# pcb_telemetria_inicial.net
KiCad netlist of a schematic drawn in EAGLE
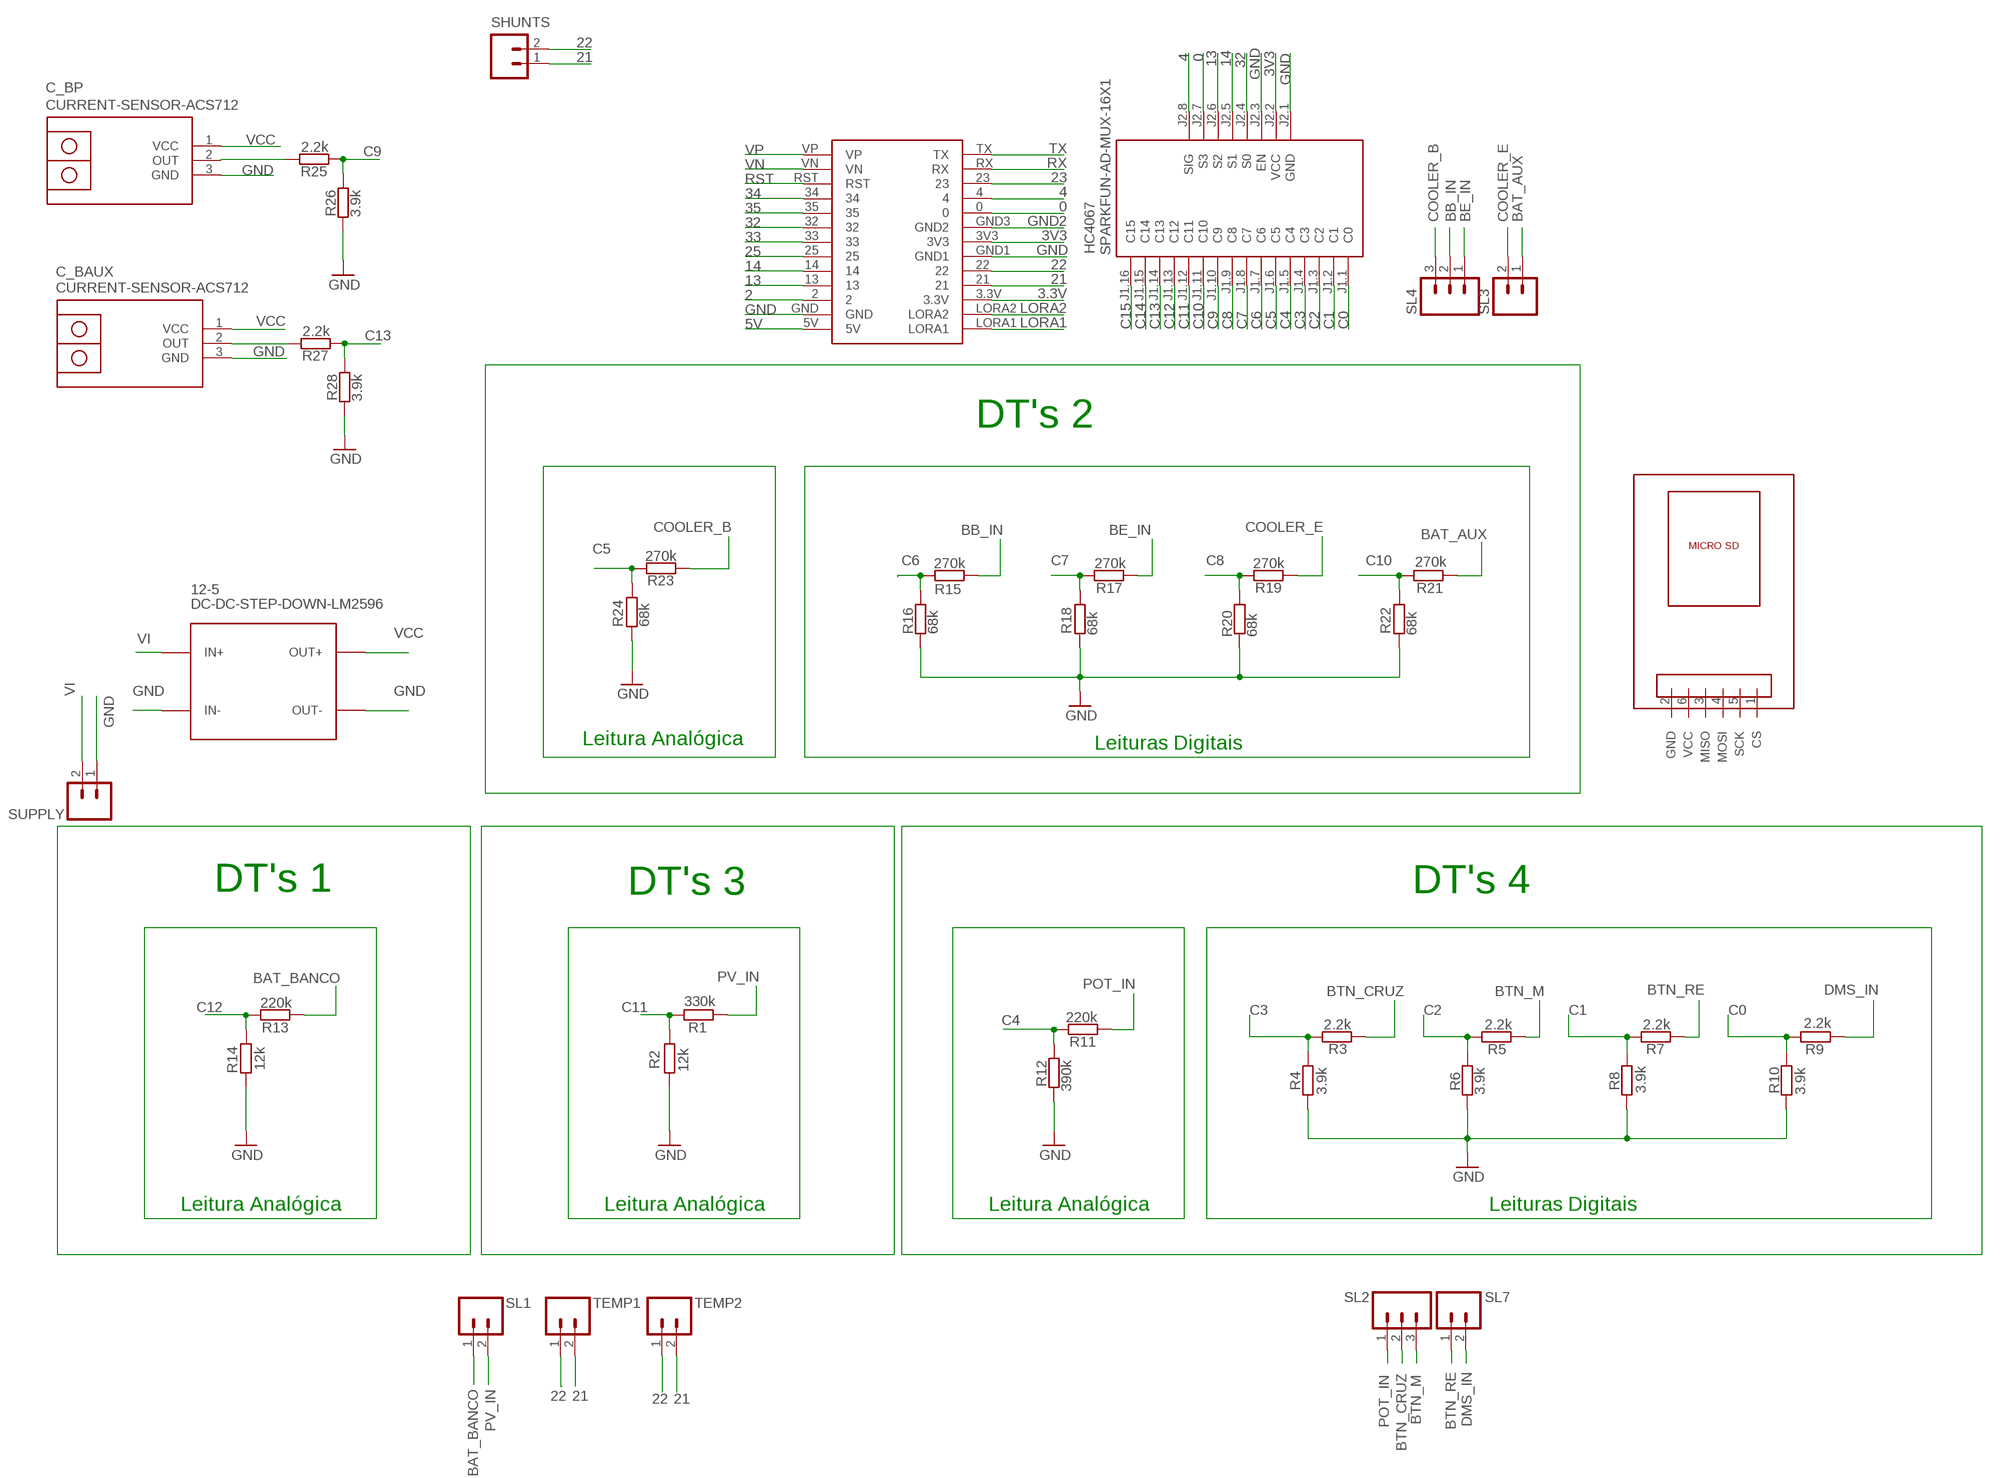
[diagram p0: schematic, sheet 1]

(export (version "E")
  (design (tool "Eeschema 10.0.6"))
  (components
    (comp (ref "12-5")
      (value "DC-DC-STEP-DOWN-LM2596")
      (footprint "eagle-import:DC-DC-STEP-DOWN-LM2596")
      (libsource (lib "eagle-import") (part "DC-DC-STEP-DOWN-LM2596"))
    )
    (comp (ref "C_BAUX")
      (value "CURRENT-SENSOR-ACS712")
      (footprint "eagle-import:CURRENT-SENSOR-ACS712")
      (libsource (lib "eagle-import") (part "CURRENT-SENSOR-ACS712"))
    )
    (comp (ref "C_BP")
      (value "CURRENT-SENSOR-ACS712")
      (footprint "eagle-import:CURRENT-SENSOR-ACS712")
      (libsource (lib "eagle-import") (part "CURRENT-SENSOR-ACS712"))
    )
    (comp (ref "HC4067")
      (value "SPARKFUN-AD-MUX-16X1")
      (footprint "eagle-import:SPARKFUN-AD-MUX-16X1")
      (libsource (lib "eagle-import") (part "SPARKFUN-AD-MUX-16X1"))
    )
    (comp (ref "R1")
      (value "330k")
      (footprint "eagle-import:0204_7")
      (libsource (lib "eagle-import") (part "R-EU_0204/7"))
    )
    (comp (ref "R2")
      (value "12k")
      (footprint "eagle-import:0204_7")
      (libsource (lib "eagle-import") (part "R-EU_0204/7"))
    )
    (comp (ref "R3")
      (value "2.2k")
      (footprint "eagle-import:0204_7")
      (libsource (lib "eagle-import") (part "R-EU_0204/7"))
    )
    (comp (ref "R4")
      (value "3.9k")
      (footprint "eagle-import:0204_7")
      (libsource (lib "eagle-import") (part "R-EU_0204/7"))
    )
    (comp (ref "R5")
      (value "2.2k")
      (footprint "eagle-import:0204_7")
      (libsource (lib "eagle-import") (part "R-EU_0204/7"))
    )
    (comp (ref "R6")
      (value "3.9k")
      (footprint "eagle-import:0204_7")
      (libsource (lib "eagle-import") (part "R-EU_0204/7"))
    )
    (comp (ref "R7")
      (value "2.2k")
      (footprint "eagle-import:0204_7")
      (libsource (lib "eagle-import") (part "R-EU_0204/7"))
    )
    (comp (ref "R8")
      (value "3.9k")
      (footprint "eagle-import:0204_7")
      (libsource (lib "eagle-import") (part "R-EU_0204/7"))
    )
    (comp (ref "R9")
      (value "2.2k")
      (footprint "eagle-import:0204_7")
      (libsource (lib "eagle-import") (part "R-EU_0204/7"))
    )
    (comp (ref "R10")
      (value "3.9k")
      (footprint "eagle-import:0204_7")
      (libsource (lib "eagle-import") (part "R-EU_0204/7"))
    )
    (comp (ref "R11")
      (value "220k")
      (footprint "eagle-import:0204_7")
      (libsource (lib "eagle-import") (part "R-EU_0204/7"))
    )
    (comp (ref "R12")
      (value "390k")
      (footprint "eagle-import:0204_7")
      (libsource (lib "eagle-import") (part "R-EU_0204/7"))
    )
    (comp (ref "R13")
      (value "220k")
      (footprint "eagle-import:0204_7")
      (libsource (lib "eagle-import") (part "R-EU_0204/7"))
    )
    (comp (ref "R14")
      (value "12k")
      (footprint "eagle-import:0204_7")
      (libsource (lib "eagle-import") (part "R-EU_0204/7"))
    )
    (comp (ref "R15")
      (value "270k")
      (footprint "eagle-import:0204_7")
      (libsource (lib "eagle-import") (part "R-EU_0204/7"))
    )
    (comp (ref "R16")
      (value "68k")
      (footprint "eagle-import:0204_7")
      (libsource (lib "eagle-import") (part "R-EU_0204/7"))
    )
    (comp (ref "R17")
      (value "270k")
      (footprint "eagle-import:0204_7")
      (libsource (lib "eagle-import") (part "R-EU_0204/7"))
    )
    (comp (ref "R18")
      (value "68k")
      (footprint "eagle-import:0204_7")
      (libsource (lib "eagle-import") (part "R-EU_0204/7"))
    )
    (comp (ref "R19")
      (value "270k")
      (footprint "eagle-import:0204_7")
      (libsource (lib "eagle-import") (part "R-EU_0204/7"))
    )
    (comp (ref "R20")
      (value "68k")
      (footprint "eagle-import:0204_7")
      (libsource (lib "eagle-import") (part "R-EU_0204/7"))
    )
    (comp (ref "R21")
      (value "270k")
      (footprint "eagle-import:0204_7")
      (libsource (lib "eagle-import") (part "R-EU_0204/7"))
    )
    (comp (ref "R22")
      (value "68k")
      (footprint "eagle-import:0204_7")
      (libsource (lib "eagle-import") (part "R-EU_0204/7"))
    )
    (comp (ref "R23")
      (value "270k")
      (footprint "eagle-import:0204_7")
      (libsource (lib "eagle-import") (part "R-EU_0204/7"))
    )
    (comp (ref "R24")
      (value "68k")
      (footprint "eagle-import:0204_7")
      (libsource (lib "eagle-import") (part "R-EU_0204/7"))
    )
    (comp (ref "R25")
      (value "2.2k")
      (footprint "eagle-import:0204_7")
      (libsource (lib "eagle-import") (part "R-EU_0204/7"))
    )
    (comp (ref "R26")
      (value "3.9k")
      (footprint "eagle-import:0204_7")
      (libsource (lib "eagle-import") (part "R-EU_0204/7"))
    )
    (comp (ref "R27")
      (value "2.2k")
      (footprint "eagle-import:0204_7")
      (libsource (lib "eagle-import") (part "R-EU_0204/7"))
    )
    (comp (ref "R28")
      (value "3.9k")
      (footprint "eagle-import:0204_7")
      (libsource (lib "eagle-import") (part "R-EU_0204/7"))
    )
    (comp (ref "SHUNTS")
      (value "M02")
      (footprint "eagle-import:02P")
      (libsource (lib "eagle-import") (part "M02"))
    )
    (comp (ref "SL1")
      (value "M02")
      (footprint "eagle-import:02P")
      (libsource (lib "eagle-import") (part "M02"))
    )
    (comp (ref "SL2")
      (value "M03")
      (footprint "eagle-import:03P")
      (libsource (lib "eagle-import") (part "M03"))
    )
    (comp (ref "SL3")
      (value "M02")
      (footprint "eagle-import:02P")
      (libsource (lib "eagle-import") (part "M02"))
    )
    (comp (ref "SL4")
      (value "M03")
      (footprint "eagle-import:03P")
      (libsource (lib "eagle-import") (part "M03"))
    )
    (comp (ref "SL7")
      (value "M02")
      (footprint "eagle-import:02P")
      (libsource (lib "eagle-import") (part "M02"))
    )
    (comp (ref "SUPPLY")
      (value "M02")
      (footprint "eagle-import:02P")
      (libsource (lib "eagle-import") (part "M02"))
    )
    (comp (ref "TEMP1")
      (value "M02")
      (footprint "eagle-import:02P")
      (libsource (lib "eagle-import") (part "M02"))
    )
    (comp (ref "TEMP2")
      (value "M02")
      (footprint "eagle-import:02P")
      (libsource (lib "eagle-import") (part "M02"))
    )
    (comp (ref "U$1")
      (value "TTGOBEAM")
      (footprint "eagle-import:TTGOBEAM")
      (libsource (lib "eagle-import") (part "TTGOBEAM"))
    )
    (comp (ref "U$2")
      (value "MICRO_SD_MODULE")
      (footprint "eagle-import:MICRO_SD")
      (libsource (lib "eagle-import") (part "MICRO_SD_MODULE"))
    )
  )
  (nets
    (net (code "1") (name "/0") (class "Default")
      (node (ref "HC4067") (pin "J2.7") (pinfunction "S3_J2.7") (pintype "bidirectional"))
      (node (ref "U$1") (pin "0") (pinfunction "0_0") (pintype "bidirectional"))
    )
    (net (code "2") (name "/2") (class "Default")
      (node (ref "U$1") (pin "2") (pinfunction "2_2") (pintype "bidirectional"))
    )
    (net (code "3") (name "/3.3V") (class "Default")
      (node (ref "U$1") (pin "3.3V") (pinfunction "3.3V_3.3V") (pintype "bidirectional"))
    )
    (net (code "4") (name "/3V3") (class "Default")
      (node (ref "HC4067") (pin "J2.2") (pinfunction "VCC_J2.2") (pintype "power_in"))
      (node (ref "U$1") (pin "3V3") (pinfunction "3V3_3V3") (pintype "bidirectional"))
    )
    (net (code "5") (name "/4") (class "Default")
      (node (ref "HC4067") (pin "J2.8") (pinfunction "SIG_J2.8") (pintype "bidirectional"))
      (node (ref "U$1") (pin "4") (pinfunction "4_4") (pintype "bidirectional"))
    )
    (net (code "6") (name "/5V") (class "Default")
      (node (ref "U$1") (pin "5V") (pinfunction "5V_5V") (pintype "bidirectional"))
    )
    (net (code "7") (name "/13") (class "Default")
      (node (ref "HC4067") (pin "J2.6") (pinfunction "S2_J2.6") (pintype "bidirectional"))
      (node (ref "U$1") (pin "13") (pinfunction "13_13") (pintype "bidirectional"))
    )
    (net (code "8") (name "/14") (class "Default")
      (node (ref "HC4067") (pin "J2.5") (pinfunction "S1_J2.5") (pintype "bidirectional"))
      (node (ref "U$1") (pin "14") (pinfunction "14_14") (pintype "bidirectional"))
    )
    (net (code "9") (name "/21") (class "Default")
      (node (ref "SHUNTS") (pin "1") (pinfunction "1_1") (pintype "passive"))
      (node (ref "TEMP1") (pin "2") (pinfunction "2_2") (pintype "passive"))
      (node (ref "TEMP2") (pin "2") (pinfunction "2_2") (pintype "passive"))
      (node (ref "U$1") (pin "21") (pinfunction "21_21") (pintype "bidirectional"))
    )
    (net (code "10") (name "/22") (class "Default")
      (node (ref "SHUNTS") (pin "2") (pinfunction "2_2") (pintype "passive"))
      (node (ref "TEMP1") (pin "1") (pinfunction "1_1") (pintype "passive"))
      (node (ref "TEMP2") (pin "1") (pinfunction "1_1") (pintype "passive"))
      (node (ref "U$1") (pin "22") (pinfunction "22_22") (pintype "bidirectional"))
    )
    (net (code "11") (name "/23") (class "Default")
      (node (ref "U$1") (pin "23") (pinfunction "23_23") (pintype "bidirectional"))
    )
    (net (code "12") (name "/25") (class "Default")
      (node (ref "U$1") (pin "25") (pinfunction "25_25") (pintype "bidirectional"))
    )
    (net (code "13") (name "/32") (class "Default")
      (node (ref "HC4067") (pin "J2.4") (pinfunction "S0_J2.4") (pintype "bidirectional"))
      (node (ref "U$1") (pin "32") (pinfunction "32_32") (pintype "bidirectional"))
    )
    (net (code "14") (name "/33") (class "Default")
      (node (ref "U$1") (pin "33") (pinfunction "33_33") (pintype "bidirectional"))
    )
    (net (code "15") (name "/34") (class "Default")
      (node (ref "U$1") (pin "34") (pinfunction "34_34") (pintype "bidirectional"))
    )
    (net (code "16") (name "/35") (class "Default")
      (node (ref "U$1") (pin "35") (pinfunction "35_35") (pintype "bidirectional"))
    )
    (net (code "17") (name "/BAT_AUX") (class "Default")
      (node (ref "R21") (pin "2") (pinfunction "2_2") (pintype "passive"))
      (node (ref "SL3") (pin "1") (pinfunction "1_1") (pintype "passive"))
    )
    (net (code "18") (name "/BAT_BANCO") (class "Default")
      (node (ref "R13") (pin "2") (pinfunction "2_2") (pintype "passive"))
      (node (ref "SL1") (pin "1") (pinfunction "1_1") (pintype "passive"))
    )
    (net (code "19") (name "/BB_IN") (class "Default")
      (node (ref "R15") (pin "1") (pinfunction "1_1") (pintype "passive"))
      (node (ref "SL4") (pin "2") (pinfunction "2_2") (pintype "passive"))
    )
    (net (code "20") (name "/BE_IN") (class "Default")
      (node (ref "R17") (pin "2") (pinfunction "2_2") (pintype "passive"))
      (node (ref "SL4") (pin "1") (pinfunction "1_1") (pintype "passive"))
    )
    (net (code "21") (name "/BTN_CRUZ") (class "Default")
      (node (ref "R3") (pin "1") (pinfunction "1_1") (pintype "passive"))
      (node (ref "SL2") (pin "2") (pinfunction "2_2") (pintype "passive"))
    )
    (net (code "22") (name "/BTN_M") (class "Default")
      (node (ref "R5") (pin "2") (pinfunction "2_2") (pintype "passive"))
      (node (ref "SL2") (pin "3") (pinfunction "3_3") (pintype "passive"))
    )
    (net (code "23") (name "/BTN_RE") (class "Default")
      (node (ref "R7") (pin "1") (pinfunction "1_1") (pintype "passive"))
      (node (ref "SL7") (pin "1") (pinfunction "1_1") (pintype "passive"))
    )
    (net (code "24") (name "/C0") (class "Default")
      (node (ref "HC4067") (pin "J1.1") (pinfunction "C0_J1.1") (pintype "bidirectional"))
      (node (ref "R10") (pin "2") (pinfunction "2_2") (pintype "passive"))
      (node (ref "R9") (pin "1") (pinfunction "1_1") (pintype "passive"))
    )
    (net (code "25") (name "/C1") (class "Default")
      (node (ref "HC4067") (pin "J1.2") (pinfunction "C1_J1.2") (pintype "bidirectional"))
      (node (ref "R7") (pin "2") (pinfunction "2_2") (pintype "passive"))
      (node (ref "R8") (pin "1") (pinfunction "1_1") (pintype "passive"))
    )
    (net (code "26") (name "/C2") (class "Default")
      (node (ref "HC4067") (pin "J1.3") (pinfunction "C2_J1.3") (pintype "bidirectional"))
      (node (ref "R5") (pin "1") (pinfunction "1_1") (pintype "passive"))
      (node (ref "R6") (pin "2") (pinfunction "2_2") (pintype "passive"))
    )
    (net (code "27") (name "/C3") (class "Default")
      (node (ref "HC4067") (pin "J1.4") (pinfunction "C3_J1.4") (pintype "bidirectional"))
      (node (ref "R3") (pin "2") (pinfunction "2_2") (pintype "passive"))
      (node (ref "R4") (pin "1") (pinfunction "1_1") (pintype "passive"))
    )
    (net (code "28") (name "/C4") (class "Default")
      (node (ref "HC4067") (pin "J1.5") (pinfunction "C4_J1.5") (pintype "bidirectional"))
      (node (ref "R11") (pin "2") (pinfunction "2_2") (pintype "passive"))
      (node (ref "R12") (pin "1") (pinfunction "1_1") (pintype "passive"))
    )
    (net (code "29") (name "/C5") (class "Default")
      (node (ref "HC4067") (pin "J1.6") (pinfunction "C5_J1.6") (pintype "bidirectional"))
      (node (ref "R23") (pin "2") (pinfunction "2_2") (pintype "passive"))
      (node (ref "R24") (pin "1") (pinfunction "1_1") (pintype "passive"))
    )
    (net (code "30") (name "/C6") (class "Default")
      (node (ref "HC4067") (pin "J1.7") (pinfunction "C6_J1.7") (pintype "bidirectional"))
      (node (ref "R15") (pin "2") (pinfunction "2_2") (pintype "passive"))
      (node (ref "R16") (pin "1") (pinfunction "1_1") (pintype "passive"))
    )
    (net (code "31") (name "/C7") (class "Default")
      (node (ref "HC4067") (pin "J1.8") (pinfunction "C7_J1.8") (pintype "bidirectional"))
      (node (ref "R17") (pin "1") (pinfunction "1_1") (pintype "passive"))
      (node (ref "R18") (pin "2") (pinfunction "2_2") (pintype "passive"))
    )
    (net (code "32") (name "/C8") (class "Default")
      (node (ref "HC4067") (pin "J1.9") (pinfunction "C8_J1.9") (pintype "bidirectional"))
      (node (ref "R19") (pin "2") (pinfunction "2_2") (pintype "passive"))
      (node (ref "R20") (pin "1") (pinfunction "1_1") (pintype "passive"))
    )
    (net (code "33") (name "/C9") (class "Default")
      (node (ref "HC4067") (pin "J1.10") (pinfunction "C9_J1.10") (pintype "bidirectional"))
      (node (ref "R25") (pin "1") (pinfunction "1_1") (pintype "passive"))
      (node (ref "R26") (pin "1") (pinfunction "1_1") (pintype "passive"))
    )
    (net (code "34") (name "/C10") (class "Default")
      (node (ref "HC4067") (pin "J1.11") (pinfunction "C10_J1.11") (pintype "bidirectional"))
      (node (ref "R21") (pin "1") (pinfunction "1_1") (pintype "passive"))
      (node (ref "R22") (pin "2") (pinfunction "2_2") (pintype "passive"))
    )
    (net (code "35") (name "/C11") (class "Default")
      (node (ref "HC4067") (pin "J1.12") (pinfunction "C11_J1.12") (pintype "bidirectional"))
      (node (ref "R1") (pin "1") (pinfunction "1_1") (pintype "passive"))
      (node (ref "R2") (pin "2") (pinfunction "2_2") (pintype "passive"))
    )
    (net (code "36") (name "/C12") (class "Default")
      (node (ref "HC4067") (pin "J1.13") (pinfunction "C12_J1.13") (pintype "bidirectional"))
      (node (ref "R13") (pin "1") (pinfunction "1_1") (pintype "passive"))
      (node (ref "R14") (pin "2") (pinfunction "2_2") (pintype "passive"))
    )
    (net (code "37") (name "/C13") (class "Default")
      (node (ref "HC4067") (pin "J1.14") (pinfunction "C13_J1.14") (pintype "bidirectional"))
      (node (ref "R27") (pin "1") (pinfunction "1_1") (pintype "passive"))
      (node (ref "R28") (pin "1") (pinfunction "1_1") (pintype "passive"))
    )
    (net (code "38") (name "/C14") (class "Default")
      (node (ref "HC4067") (pin "J1.15") (pinfunction "C14_J1.15") (pintype "bidirectional"))
    )
    (net (code "39") (name "/C15") (class "Default")
      (node (ref "HC4067") (pin "J1.16") (pinfunction "C15_J1.16") (pintype "bidirectional"))
    )
    (net (code "40") (name "/COOLER_B") (class "Default")
      (node (ref "R23") (pin "1") (pinfunction "1_1") (pintype "passive"))
      (node (ref "SL4") (pin "3") (pinfunction "3_3") (pintype "passive"))
    )
    (net (code "41") (name "/COOLER_E") (class "Default")
      (node (ref "R19") (pin "1") (pinfunction "1_1") (pintype "passive"))
      (node (ref "SL3") (pin "2") (pinfunction "2_2") (pintype "passive"))
    )
    (net (code "42") (name "/DMS_IN") (class "Default")
      (node (ref "R9") (pin "2") (pinfunction "2_2") (pintype "passive"))
      (node (ref "SL7") (pin "2") (pinfunction "2_2") (pintype "passive"))
    )
    (net (code "43") (name "/GND2") (class "Default")
      (node (ref "U$1") (pin "GND3") (pinfunction "GND2_GND3") (pintype "bidirectional"))
    )
    (net (code "44") (name "/LORA1") (class "Default")
      (node (ref "U$1") (pin "LORA1") (pinfunction "LORA1_LORA1") (pintype "bidirectional"))
    )
    (net (code "45") (name "/LORA2") (class "Default")
      (node (ref "U$1") (pin "LORA2") (pinfunction "LORA2_LORA2") (pintype "bidirectional"))
    )
    (net (code "46") (name "/POT_IN") (class "Default")
      (node (ref "R11") (pin "1") (pinfunction "1_1") (pintype "passive"))
      (node (ref "SL2") (pin "1") (pinfunction "1_1") (pintype "passive"))
    )
    (net (code "47") (name "/PV_IN") (class "Default")
      (node (ref "R1") (pin "2") (pinfunction "2_2") (pintype "passive"))
      (node (ref "SL1") (pin "2") (pinfunction "2_2") (pintype "passive"))
    )
    (net (code "48") (name "/RST") (class "Default")
      (node (ref "U$1") (pin "RST") (pinfunction "RST_RST") (pintype "bidirectional"))
    )
    (net (code "49") (name "/RX") (class "Default")
      (node (ref "U$1") (pin "RX") (pinfunction "RX_RX") (pintype "bidirectional"))
    )
    (net (code "50") (name "/TX") (class "Default")
      (node (ref "U$1") (pin "TX") (pinfunction "TX_TX") (pintype "bidirectional"))
    )
    (net (code "51") (name "/VCC") (class "Default")
      (node (ref "12-5") (pin "OUT+") (pinfunction "OUT+_OUT+") (pintype "bidirectional"))
      (node (ref "C_BAUX") (pin "1") (pinfunction "VCC_1") (pintype "power_in"))
      (node (ref "C_BP") (pin "1") (pinfunction "VCC_1") (pintype "power_in"))
    )
    (net (code "52") (name "/VI") (class "Default")
      (node (ref "12-5") (pin "IN+") (pinfunction "IN+_IN+") (pintype "bidirectional"))
      (node (ref "SUPPLY") (pin "2") (pinfunction "2_2") (pintype "passive"))
    )
    (net (code "53") (name "/VN") (class "Default")
      (node (ref "U$1") (pin "VN") (pinfunction "VN_VN") (pintype "bidirectional"))
    )
    (net (code "54") (name "/VP") (class "Default")
      (node (ref "U$1") (pin "VP") (pinfunction "VP_VP") (pintype "bidirectional"))
    )
    (net (code "55") (name "GND") (class "Default")
      (node (ref "12-5") (pin "IN-") (pinfunction "IN-_IN-") (pintype "bidirectional"))
      (node (ref "12-5") (pin "OUT-") (pinfunction "OUT-_OUT-") (pintype "bidirectional"))
      (node (ref "C_BAUX") (pin "3") (pinfunction "GND_3") (pintype "power_in"))
      (node (ref "C_BP") (pin "3") (pinfunction "GND_3") (pintype "power_in"))
      (node (ref "HC4067") (pin "J2.1") (pinfunction "GND_J2.1") (pintype "power_in"))
      (node (ref "HC4067") (pin "J2.3") (pinfunction "EN_J2.3") (pintype "input"))
      (node (ref "R10") (pin "1") (pinfunction "1_1") (pintype "passive"))
      (node (ref "R12") (pin "2") (pinfunction "2_2") (pintype "passive"))
      (node (ref "R14") (pin "1") (pinfunction "1_1") (pintype "passive"))
      (node (ref "R16") (pin "2") (pinfunction "2_2") (pintype "passive"))
      (node (ref "R18") (pin "1") (pinfunction "1_1") (pintype "passive"))
      (node (ref "R2") (pin "1") (pinfunction "1_1") (pintype "passive"))
      (node (ref "R20") (pin "2") (pinfunction "2_2") (pintype "passive"))
      (node (ref "R22") (pin "1") (pinfunction "1_1") (pintype "passive"))
      (node (ref "R24") (pin "2") (pinfunction "2_2") (pintype "passive"))
      (node (ref "R26") (pin "2") (pinfunction "2_2") (pintype "passive"))
      (node (ref "R28") (pin "2") (pinfunction "2_2") (pintype "passive"))
      (node (ref "R4") (pin "2") (pinfunction "2_2") (pintype "passive"))
      (node (ref "R6") (pin "1") (pinfunction "1_1") (pintype "passive"))
      (node (ref "R8") (pin "2") (pinfunction "2_2") (pintype "passive"))
      (node (ref "SUPPLY") (pin "1") (pinfunction "1_1") (pintype "passive"))
      (node (ref "U$1") (pin "GND") (pinfunction "GND_GND") (pintype "bidirectional"))
      (node (ref "U$1") (pin "GND1") (pinfunction "GND1_GND1") (pintype "bidirectional"))
    )
    (net (code "56") (name "Net-(C_BAUX-OUT)") (class "Default")
      (node (ref "C_BAUX") (pin "2") (pinfunction "OUT_2") (pintype "output"))
      (node (ref "R27") (pin "2") (pinfunction "2_2") (pintype "passive"))
    )
    (net (code "57") (name "Net-(C_BP-OUT)") (class "Default")
      (node (ref "C_BP") (pin "2") (pinfunction "OUT_2") (pintype "output"))
      (node (ref "R25") (pin "2") (pinfunction "2_2") (pintype "passive"))
    )
    (net (code "58") (name "unconnected-(U$2-CS-Pad1)") (class "Default")
      (node (ref "U$2") (pin "1") (pinfunction "CS_1") (pintype "bidirectional"))
    )
    (net (code "59") (name "unconnected-(U$2-GND-Pad2)") (class "Default")
      (node (ref "U$2") (pin "2") (pinfunction "GND_2") (pintype "input"))
    )
    (net (code "60") (name "unconnected-(U$2-MISO-Pad3)") (class "Default")
      (node (ref "U$2") (pin "3") (pinfunction "MISO_3") (pintype "bidirectional"))
    )
    (net (code "61") (name "unconnected-(U$2-MOSI-Pad4)") (class "Default")
      (node (ref "U$2") (pin "4") (pinfunction "MOSI_4") (pintype "bidirectional"))
    )
    (net (code "62") (name "unconnected-(U$2-SCK-Pad5)") (class "Default")
      (node (ref "U$2") (pin "5") (pinfunction "SCK_5") (pintype "bidirectional"))
    )
    (net (code "63") (name "unconnected-(U$2-VCC-Pad6)") (class "Default")
      (node (ref "U$2") (pin "6") (pinfunction "VCC_6") (pintype "input"))
    )
  )
)
